# board.net
KiCad netlist of a schematic drawn in EAGLE
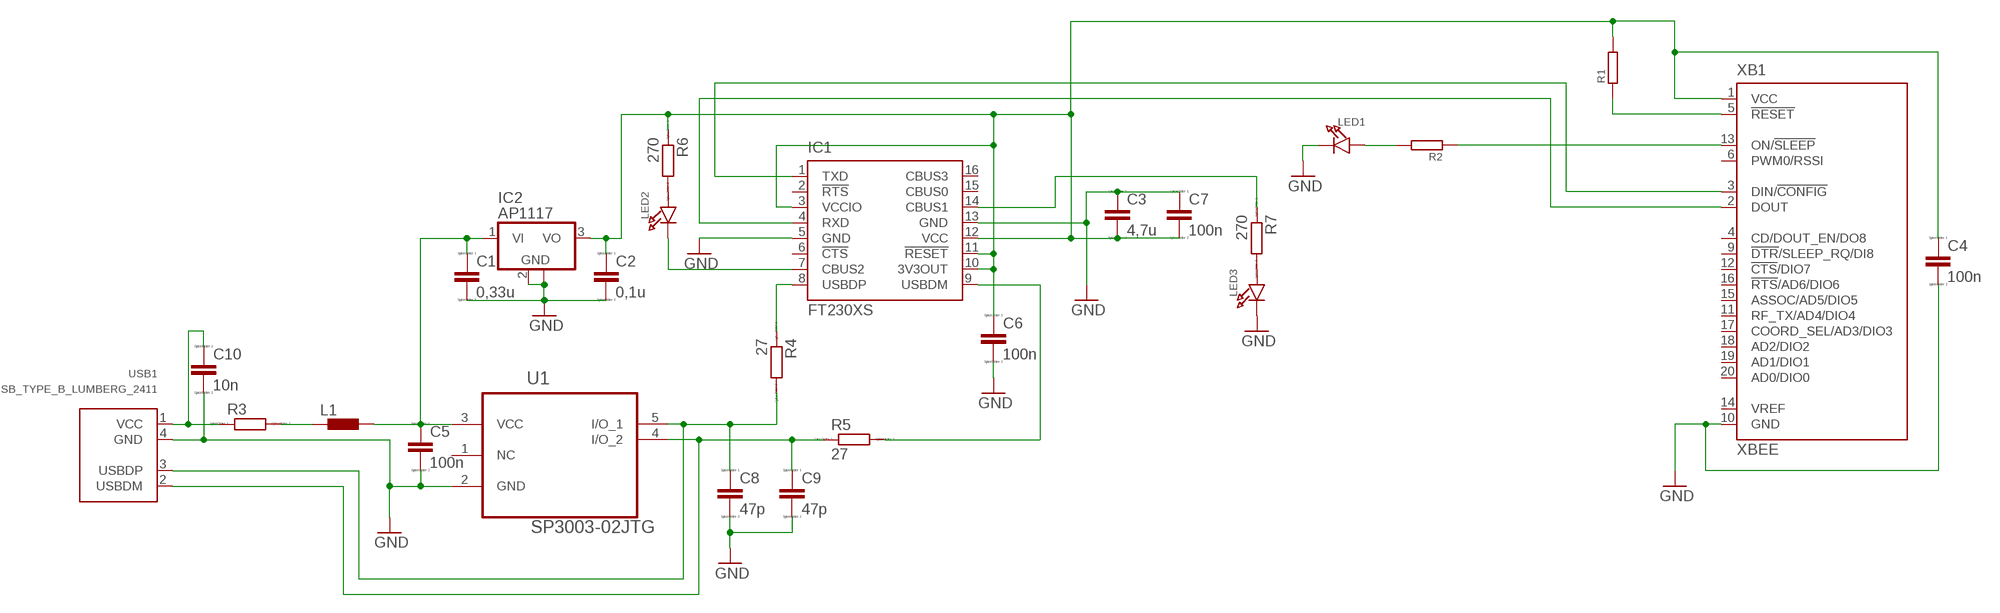
[diagram p0: schematic, sheet 1]

(export (version "E")
  (design (tool "Eeschema 10.0.6"))
  (components
    (comp (ref "C1")
      (value "0,33u")
      (footprint "eagle-import:C0805K")
      (libsource (lib "eagle-import") (part "C-EUC0805K"))
    )
    (comp (ref "C2")
      (value "0,1u")
      (footprint "eagle-import:C0805K")
      (libsource (lib "eagle-import") (part "C-EUC0805K"))
    )
    (comp (ref "C3")
      (value "4,7u")
      (footprint "eagle-import:C0805K")
      (libsource (lib "eagle-import") (part "C-EUC0805K"))
    )
    (comp (ref "C4")
      (value "100n")
      (footprint "eagle-import:C0805K")
      (libsource (lib "eagle-import") (part "C-EUC0805K"))
    )
    (comp (ref "C5")
      (value "100n")
      (footprint "eagle-import:C0805K")
      (libsource (lib "eagle-import") (part "C-EUC0805K"))
    )
    (comp (ref "C6")
      (value "100n")
      (footprint "eagle-import:C0805K")
      (libsource (lib "eagle-import") (part "C-EUC0805K"))
    )
    (comp (ref "C7")
      (value "100n")
      (footprint "eagle-import:C0805K")
      (libsource (lib "eagle-import") (part "C-EUC0805K"))
    )
    (comp (ref "C8")
      (value "47p")
      (footprint "eagle-import:C0805K")
      (libsource (lib "eagle-import") (part "C-EUC0805K"))
    )
    (comp (ref "C9")
      (value "47p")
      (footprint "eagle-import:C0805K")
      (libsource (lib "eagle-import") (part "C-EUC0805K"))
    )
    (comp (ref "C10")
      (value "10n")
      (footprint "eagle-import:C0805K")
      (libsource (lib "eagle-import") (part "C-EUC0805K"))
    )
    (comp (ref "IC1")
      (value "FT230XS")
      (footprint "eagle-import:SSOP16")
      (libsource (lib "eagle-import") (part "FT230XS"))
    )
    (comp (ref "IC2")
      (value "AP1117")
      (footprint "eagle-import:SOT223")
      (libsource (lib "eagle-import") (part "UA78MDCY05"))
    )
    (comp (ref "L1")
      (value "BLM15HB121SN1")
      (footprint "eagle-import:0402")
      (libsource (lib "eagle-import") (part "BLM15HB121SN1"))
    )
    (comp (ref "LED1")
      (value "LED1206")
      (footprint "eagle-import:CHIPLED_1206")
      (libsource (lib "eagle-import") (part "LED1206"))
    )
    (comp (ref "LED2")
      (value "LED1206")
      (footprint "eagle-import:CHIPLED_1206")
      (libsource (lib "eagle-import") (part "LED1206"))
    )
    (comp (ref "LED3")
      (value "LED1206")
      (footprint "eagle-import:CHIPLED_1206")
      (libsource (lib "eagle-import") (part "LED1206"))
    )
    (comp (ref "R1")
      (value "RESISTOR_0805")
      (footprint "eagle-import:0805")
      (libsource (lib "eagle-import") (part "RESISTOR_0805"))
    )
    (comp (ref "R2")
      (value "RESISTOR_0805")
      (footprint "eagle-import:0805")
      (libsource (lib "eagle-import") (part "RESISTOR_0805"))
    )
    (comp (ref "R3")
      (value "RR1206")
      (footprint "eagle-import:R1206")
      (libsource (lib "eagle-import") (part "RR1206"))
    )
    (comp (ref "R4")
      (value "27")
      (footprint "eagle-import:R1206")
      (libsource (lib "eagle-import") (part "RR1206"))
    )
    (comp (ref "R5")
      (value "27")
      (footprint "eagle-import:R1206")
      (libsource (lib "eagle-import") (part "RR1206"))
    )
    (comp (ref "R6")
      (value "270")
      (footprint "eagle-import:R1206")
      (libsource (lib "eagle-import") (part "RR1206"))
    )
    (comp (ref "R7")
      (value "270")
      (footprint "eagle-import:R1206")
      (libsource (lib "eagle-import") (part "RR1206"))
    )
    (comp (ref "U1")
      (value "SP3003-02JTG")
      (footprint "eagle-import:SOT65P220X110-5N")
      (libsource (lib "eagle-import") (part "SP3003-02JTG"))
    )
    (comp (ref "USB1")
      (value "USB_TYPE_B_LUMBERG_2411")
      (footprint "eagle-import:USB_TYPE_B_LUMBERG_2411")
      (libsource (lib "eagle-import") (part "USB_TYPE_B_LUMBERG_2411"))
    )
    (comp (ref "XB1")
      (value "XBEE")
      (footprint "eagle-import:XBEE")
      (fields (field (name "MPN") "XBP24-Z7UIT-004"))
      (libsource (lib "eagle-import") (part "XBEE"))
    )
  )
  (nets
    (net (code "1") (name "GND") (class "Default")
      (node (ref "C1") (pin "2") (pinfunction "2_2") (pintype "passive"))
      (node (ref "C10") (pin "2") (pinfunction "2_2") (pintype "passive"))
      (node (ref "C2") (pin "2") (pinfunction "2_2") (pintype "passive"))
      (node (ref "C3") (pin "1") (pinfunction "1_1") (pintype "passive"))
      (node (ref "C4") (pin "2") (pinfunction "2_2") (pintype "passive"))
      (node (ref "C5") (pin "2") (pinfunction "2_2") (pintype "passive"))
      (node (ref "C6") (pin "2") (pinfunction "2_2") (pintype "passive"))
      (node (ref "C7") (pin "1") (pinfunction "1_1") (pintype "passive"))
      (node (ref "C8") (pin "2") (pinfunction "2_2") (pintype "passive"))
      (node (ref "C9") (pin "2") (pinfunction "2_2") (pintype "passive"))
      (node (ref "IC1") (pin "13") (pinfunction "GND_13") (pintype "power_in"))
      (node (ref "IC1") (pin "5") (pinfunction "GND_5") (pintype "power_in"))
      (node (ref "IC2") (pin "2") (pinfunction "GND_2") (pintype "passive"))
      (node (ref "IC2") (pin "4") (pinfunction "GND_4") (pintype "passive"))
      (node (ref "LED1") (pin "C") (pinfunction "C_C") (pintype "passive"))
      (node (ref "LED3") (pin "C") (pinfunction "C_C") (pintype "passive"))
      (node (ref "U1") (pin "2") (pinfunction "GND_2") (pintype "passive"))
      (node (ref "USB1") (pin "4") (pinfunction "GND_4") (pintype "bidirectional"))
      (node (ref "XB1") (pin "10") (pinfunction "GND_10") (pintype "power_in"))
    )
    (net (code "2") (name "Net-(IC1-3V3OUT)") (class "Default")
      (node (ref "C2") (pin "1") (pinfunction "1_1") (pintype "passive"))
      (node (ref "C3") (pin "2") (pinfunction "2_2") (pintype "passive"))
      (node (ref "C4") (pin "1") (pinfunction "1_1") (pintype "passive"))
      (node (ref "C6") (pin "1") (pinfunction "1_1") (pintype "passive"))
      (node (ref "C7") (pin "2") (pinfunction "2_2") (pintype "passive"))
      (node (ref "IC1") (pin "10") (pinfunction "3V3OUT_10") (pintype "output"))
      (node (ref "IC1") (pin "11") (pinfunction "~{RESET}_11") (pintype "input"))
      (node (ref "IC1") (pin "12") (pinfunction "VCC_12") (pintype "power_in"))
      (node (ref "IC1") (pin "3") (pinfunction "VCCIO_3") (pintype "power_in"))
      (node (ref "IC2") (pin "3") (pinfunction "VO_3") (pintype "passive"))
      (node (ref "R1") (pin "2") (pinfunction "2_2") (pintype "bidirectional"))
      (node (ref "R6") (pin "1") (pinfunction "1_1") (pintype "passive"))
      (node (ref "XB1") (pin "1") (pinfunction "VCC_1") (pintype "power_in"))
    )
    (net (code "3") (name "Net-(IC1-CBUS1)") (class "Default")
      (node (ref "IC1") (pin "14") (pinfunction "CBUS1_14") (pintype "bidirectional"))
      (node (ref "R7") (pin "1") (pinfunction "1_1") (pintype "passive"))
    )
    (net (code "4") (name "Net-(IC1-CBUS2)") (class "Default")
      (node (ref "IC1") (pin "7") (pinfunction "CBUS2_7") (pintype "bidirectional"))
      (node (ref "LED2") (pin "C") (pinfunction "C_C") (pintype "passive"))
    )
    (net (code "5") (name "Net-(IC1-RXD)") (class "Default")
      (node (ref "IC1") (pin "4") (pinfunction "RXD_4") (pintype "input"))
      (node (ref "XB1") (pin "2") (pinfunction "DOUT_2") (pintype "output"))
    )
    (net (code "6") (name "Net-(IC1-TXD)") (class "Default")
      (node (ref "IC1") (pin "1") (pinfunction "TXD_1") (pintype "output"))
      (node (ref "XB1") (pin "3") (pinfunction "DIN/~{CONFIG}_3") (pintype "input"))
    )
    (net (code "7") (name "Net-(IC1-USBDM)") (class "Default")
      (node (ref "IC1") (pin "9") (pinfunction "USBDM_9") (pintype "input"))
      (node (ref "R5") (pin "2") (pinfunction "2_2") (pintype "passive"))
    )
    (net (code "8") (name "Net-(IC1-USBDP)") (class "Default")
      (node (ref "IC1") (pin "8") (pinfunction "USBDP_8") (pintype "input"))
      (node (ref "R4") (pin "1") (pinfunction "1_1") (pintype "passive"))
    )
    (net (code "9") (name "Net-(IC2-VI)") (class "Default")
      (node (ref "C1") (pin "1") (pinfunction "1_1") (pintype "passive"))
      (node (ref "C5") (pin "1") (pinfunction "1_1") (pintype "passive"))
      (node (ref "IC2") (pin "1") (pinfunction "VI_1") (pintype "input"))
      (node (ref "L1") (pin "2") (pinfunction "2_2") (pintype "passive"))
      (node (ref "U1") (pin "3") (pinfunction "VCC_3") (pintype "power_in"))
    )
    (net (code "10") (name "Net-(L1-Pad1)") (class "Default")
      (node (ref "L1") (pin "1") (pinfunction "1_1") (pintype "passive"))
      (node (ref "R3") (pin "2") (pinfunction "2_2") (pintype "passive"))
    )
    (net (code "11") (name "Net-(LED1-PadA)") (class "Default")
      (node (ref "LED1") (pin "A") (pinfunction "A_A") (pintype "passive"))
      (node (ref "R2") (pin "2") (pinfunction "2_2") (pintype "bidirectional"))
    )
    (net (code "12") (name "Net-(LED2-PadA)") (class "Default")
      (node (ref "LED2") (pin "A") (pinfunction "A_A") (pintype "passive"))
      (node (ref "R6") (pin "2") (pinfunction "2_2") (pintype "passive"))
    )
    (net (code "13") (name "Net-(LED3-PadA)") (class "Default")
      (node (ref "LED3") (pin "A") (pinfunction "A_A") (pintype "passive"))
      (node (ref "R7") (pin "2") (pinfunction "2_2") (pintype "passive"))
    )
    (net (code "14") (name "Net-(U1-I{slash}O_1)") (class "Default")
      (node (ref "C8") (pin "1") (pinfunction "1_1") (pintype "passive"))
      (node (ref "R4") (pin "2") (pinfunction "2_2") (pintype "passive"))
      (node (ref "U1") (pin "5") (pinfunction "I/O_1_5") (pintype "bidirectional"))
      (node (ref "USB1") (pin "3") (pinfunction "USBDP_3") (pintype "bidirectional"))
    )
    (net (code "15") (name "Net-(U1-I{slash}O_2)") (class "Default")
      (node (ref "C9") (pin "1") (pinfunction "1_1") (pintype "passive"))
      (node (ref "R5") (pin "1") (pinfunction "1_1") (pintype "passive"))
      (node (ref "U1") (pin "4") (pinfunction "I/O_2_4") (pintype "bidirectional"))
      (node (ref "USB1") (pin "2") (pinfunction "USBDM_2") (pintype "bidirectional"))
    )
    (net (code "16") (name "Net-(USB1-VCC)") (class "Default")
      (node (ref "C10") (pin "1") (pinfunction "1_1") (pintype "passive"))
      (node (ref "R3") (pin "1") (pinfunction "1_1") (pintype "passive"))
      (node (ref "USB1") (pin "1") (pinfunction "VCC_1") (pintype "bidirectional"))
    )
    (net (code "17") (name "Net-(XB1-ON{slash}~{SLEEP})") (class "Default")
      (node (ref "R2") (pin "1") (pinfunction "1_1") (pintype "bidirectional"))
      (node (ref "XB1") (pin "13") (pinfunction "ON/~{SLEEP}_13") (pintype "output"))
    )
    (net (code "18") (name "Net-(XB1-~{RESET})") (class "Default")
      (node (ref "R1") (pin "1") (pinfunction "1_1") (pintype "bidirectional"))
      (node (ref "XB1") (pin "5") (pinfunction "~{RESET}_5") (pintype "input"))
    )
    (net (code "19") (name "unconnected-(IC1-CBUS0-Pad15)") (class "Default")
      (node (ref "IC1") (pin "15") (pinfunction "CBUS0_15") (pintype "bidirectional"))
    )
    (net (code "20") (name "unconnected-(IC1-CBUS3-Pad16)") (class "Default")
      (node (ref "IC1") (pin "16") (pinfunction "CBUS3_16") (pintype "bidirectional"))
    )
    (net (code "21") (name "unconnected-(IC1-~{CTS}-Pad6)") (class "Default")
      (node (ref "IC1") (pin "6") (pinfunction "~{CTS}_6") (pintype "input"))
    )
    (net (code "22") (name "unconnected-(IC1-~{RTS}-Pad2)") (class "Default")
      (node (ref "IC1") (pin "2") (pinfunction "~{RTS}_2") (pintype "output"))
    )
    (net (code "23") (name "unconnected-(U1-NC-Pad1)") (class "Default")
      (node (ref "U1") (pin "1") (pinfunction "NC_1") (pintype "no_connect"))
    )
    (net (code "24") (name "unconnected-(XB1-AD0{slash}DIO0-Pad20)") (class "Default")
      (node (ref "XB1") (pin "20") (pinfunction "AD0/DIO0_20") (pintype "bidirectional"))
    )
    (net (code "25") (name "unconnected-(XB1-AD1{slash}DIO1-Pad19)") (class "Default")
      (node (ref "XB1") (pin "19") (pinfunction "AD1/DIO1_19") (pintype "bidirectional"))
    )
    (net (code "26") (name "unconnected-(XB1-AD2{slash}DIO2-Pad18)") (class "Default")
      (node (ref "XB1") (pin "18") (pinfunction "AD2/DIO2_18") (pintype "bidirectional"))
    )
    (net (code "27") (name "unconnected-(XB1-ASSOC{slash}AD5{slash}DIO5-Pad15)") (class "Default")
      (node (ref "XB1") (pin "15") (pinfunction "ASSOC/AD5/DIO5_15") (pintype "bidirectional"))
    )
    (net (code "28") (name "unconnected-(XB1-CD{slash}DOUT_EN{slash}DO8-Pad4)") (class "Default")
      (node (ref "XB1") (pin "4") (pinfunction "CD/DOUT_EN/DO8_4") (pintype "output"))
    )
    (net (code "29") (name "unconnected-(XB1-COORD_SEL{slash}AD3{slash}DIO3-Pad17)") (class "Default")
      (node (ref "XB1") (pin "17") (pinfunction "COORD_SEL/AD3/DIO3_17") (pintype "bidirectional"))
    )
    (net (code "30") (name "unconnected-(XB1-PWM0{slash}RSSI-Pad6)") (class "Default")
      (node (ref "XB1") (pin "6") (pinfunction "PWM0/RSSI_6") (pintype "output"))
    )
    (net (code "31") (name "unconnected-(XB1-RF_TX{slash}AD4{slash}DIO4-Pad11)") (class "Default")
      (node (ref "XB1") (pin "11") (pinfunction "RF_TX/AD4/DIO4_11") (pintype "bidirectional"))
    )
    (net (code "32") (name "unconnected-(XB1-VREF-Pad14)") (class "Default")
      (node (ref "XB1") (pin "14") (pinfunction "VREF_14") (pintype "input"))
    )
    (net (code "33") (name "unconnected-(XB1-~{CTS}{slash}DIO7-Pad12)") (class "Default")
      (node (ref "XB1") (pin "12") (pinfunction "~{CTS}/DIO7_12") (pintype "bidirectional"))
    )
    (net (code "34") (name "unconnected-(XB1-~{DTR}{slash}SLEEP_RQ{slash}DI8-Pad9)") (class "Default")
      (node (ref "XB1") (pin "9") (pinfunction "~{DTR}/SLEEP_RQ/DI8_9") (pintype "bidirectional"))
    )
    (net (code "35") (name "unconnected-(XB1-~{RTS}{slash}AD6{slash}DIO6-Pad16)") (class "Default")
      (node (ref "XB1") (pin "16") (pinfunction "~{RTS}/AD6/DIO6_16") (pintype "bidirectional"))
    )
  )
)
